# COOLING.net
KiCad netlist of a schematic drawn in Altium Designer
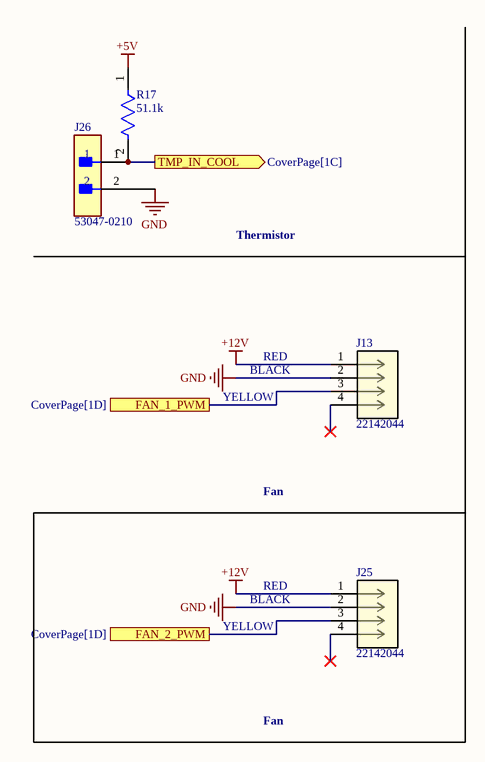
[diagram p0: COOLING.SchDoc]

(export (version "E")
  (design (tool "Eeschema 10.0.6"))
  (components
    (comp (ref "J13")
      (value "22142044")
      (footprint "CONN_SDA-4455_04_BE_MOL")
      (description "No Description Available")
      (libsource (lib "Northeastern University - Generate") (part "22142044"))
    )
    (comp (ref "J25")
      (value "22142044")
      (footprint "CONN_SDA-4455_04_BE_MOL")
      (description "No Description Available")
      (libsource (lib "Northeastern University - Generate") (part "22142044"))
    )
    (comp (ref "J26")
      (value "53047-0210")
      (footprint "FP-53047-0210-MFG")
      (description "CONN HEADER VERT 2POS 1.25MM")
      (fields
        (field (name "OCTOPART") "https://octopart.com/53047-0210-molex-276772")
        (field (name "MANUFACTURER") "Molex")
      )
      (libsource (lib "Altium Content Vault") (part "3bc925449376181038e59eaffc5286c"))
    )
    (comp (ref "R17")
      (value "51.1k")
      (footprint "FP-RG2012-MFG")
      (description "Automotive Metal Thin Film Chip Resistor, 0805, 51.1kΩ, 0.1%, 25ppm/°C, 0.125W, 150V")
      (fields (field (name "TOLERANCE") "0.1%"))
      (libsource (lib "Altium Content Vault") (part "1029c3af85768c4190bb7ad29bc67b5"))
    )
  )
  (nets
    (net (code "1") (name "+5V") (class "Default")
      (node (ref "R17") (pin "1") (pinfunction "1_1") (pintype "passive"))
    )
    (net (code "2") (name "+12V") (class "Default")
      (node (ref "J13") (pin "1") (pinfunction "1_1") (pintype "passive"))
      (node (ref "J25") (pin "1") (pinfunction "1_1") (pintype "passive"))
    )
    (net (code "3") (name "/FAN_1_PWM") (class "Default")
      (node (ref "J13") (pin "3") (pinfunction "3_3") (pintype "passive"))
    )
    (net (code "4") (name "/FAN_2_PWM") (class "Default")
      (node (ref "J25") (pin "3") (pinfunction "3_3") (pintype "passive"))
    )
    (net (code "5") (name "/TMP_IN_COOL") (class "Default")
      (node (ref "J26") (pin "1") (pinfunction "1_1") (pintype "passive"))
      (node (ref "R17") (pin "2") (pinfunction "2_2") (pintype "passive"))
    )
    (net (code "6") (name "GND") (class "Default")
      (node (ref "J13") (pin "2") (pinfunction "2_2") (pintype "passive"))
      (node (ref "J25") (pin "2") (pinfunction "2_2") (pintype "passive"))
      (node (ref "J26") (pin "2") (pinfunction "2_2") (pintype "passive"))
    )
    (net (code "7") (name "unconnected-(J13-Pad4)") (class "Default")
      (node (ref "J13") (pin "4") (pinfunction "4_4") (pintype "passive+no_connect"))
    )
    (net (code "8") (name "unconnected-(J25-Pad4)") (class "Default")
      (node (ref "J25") (pin "4") (pinfunction "4_4") (pintype "passive+no_connect"))
    )
  )
)
